# MINI-STM32.net
KiCad netlist of a schematic drawn in Altium Designer
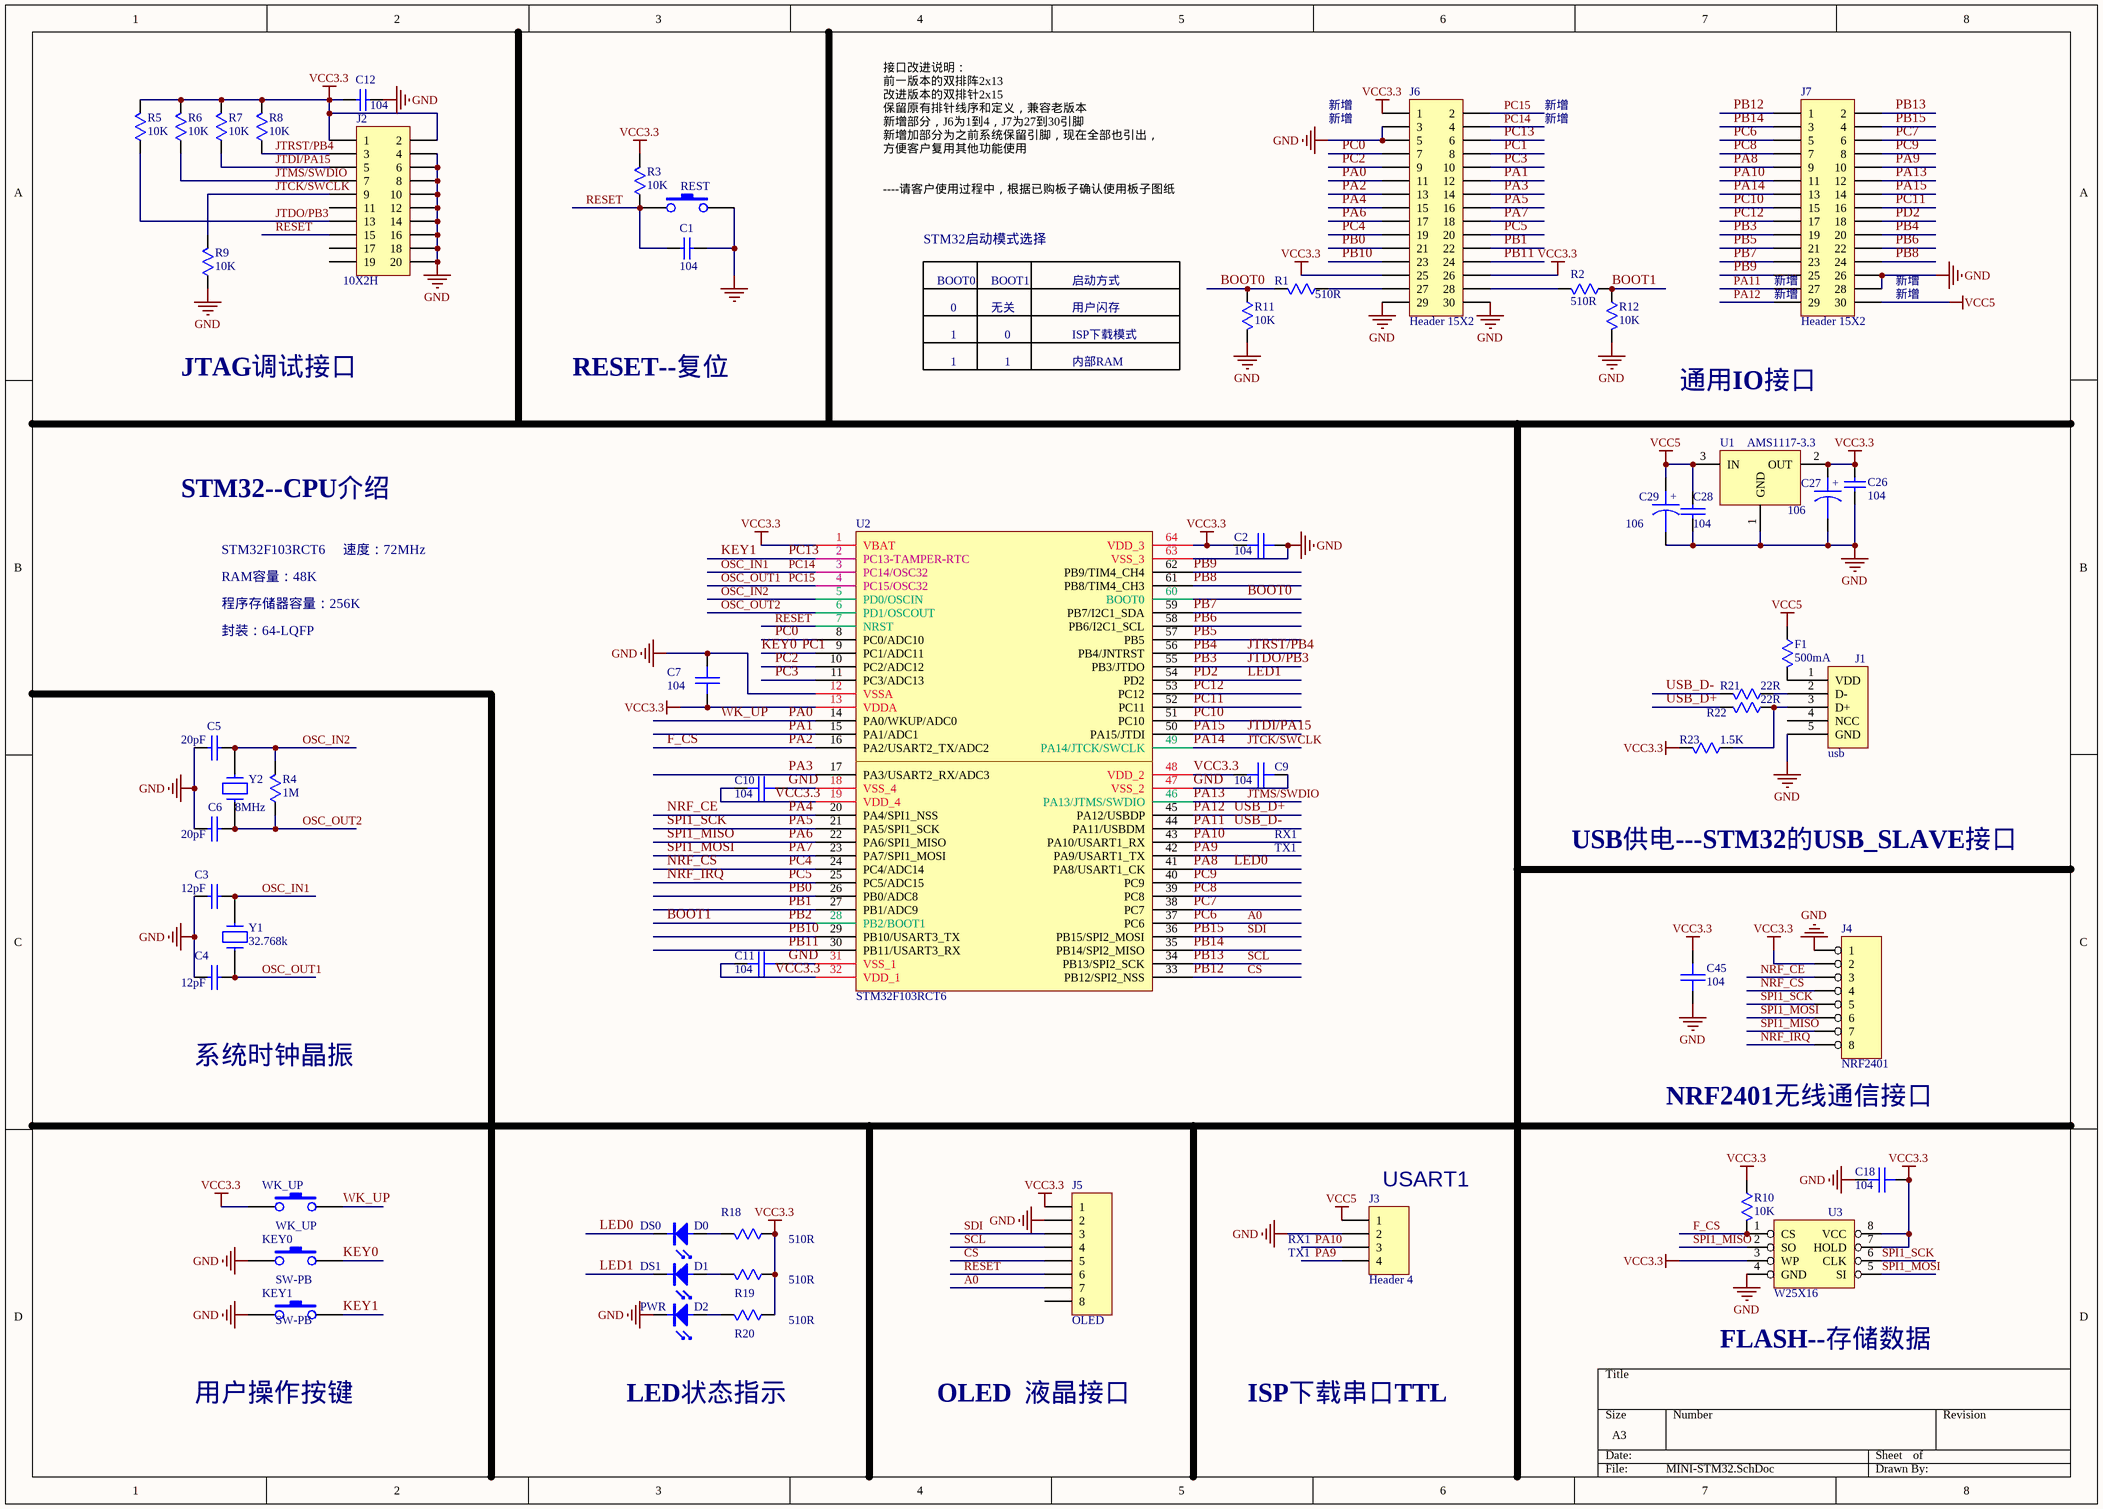
[diagram p0: MINI-STM32.SchDoc]

(export (version "E")
  (design (tool "Eeschema 10.0.6"))
  (components
    (comp (ref "C1")
      (value "104")
      (footprint "0603C")
      (description "GRM39 X7R102K50PT")
      (fields (field (name "PUBLISHER") "Altium Limited"))
      (libsource (lib "Miscellaneous Devices") (part "CAP"))
    )
    (comp (ref "C2") (value "104") (footprint "0603J") (libsource (lib "YT1_SCH_99SE") (part "CAP")))
    (comp (ref "C3")
      (value "12pF")
      (footprint "0603J")
      (description "CAP CHIP 20P 50V(+-5% C0G 0603)")
      (libsource (lib "") (part "CAP_1"))
    )
    (comp (ref "C4")
      (value "12pF")
      (footprint "0603J")
      (description "CAP CHIP 20P 50V(+-5% C0G 0603)")
      (libsource (lib "") (part "CAP_1"))
    )
    (comp (ref "C5")
      (value "20pF")
      (footprint "0603J")
      (description "CAP CHIP 20P 50V(+-5% C0G 0603)")
      (libsource (lib "") (part "CAP_1"))
    )
    (comp (ref "C6")
      (value "20pF")
      (footprint "0603J")
      (description "CAP CHIP 20P 50V(+-5% C0G 0603)")
      (libsource (lib "") (part "CAP_1"))
    )
    (comp (ref "C7") (value "104") (footprint "0603J") (libsource (lib "YT1_SCH_99SE") (part "CAP")))
    (comp (ref "C9") (value "104") (footprint "0603J") (libsource (lib "YT1_SCH_99SE") (part "CAP")))
    (comp (ref "C10") (value "104") (footprint "0603J") (libsource (lib "YT1_SCH_99SE") (part "CAP")))
    (comp (ref "C11") (value "104") (footprint "0603J") (libsource (lib "YT1_SCH_99SE") (part "CAP")))
    (comp (ref "C12")
      (value "104")
      (footprint "0603C")
      (description "GRM39 X7R102K50PT")
      (fields (field (name "PUBLISHER") "Altium Limited"))
      (libsource (lib "Miscellaneous Devices") (part "CAP"))
    )
    (comp (ref "C18") (value "104") (footprint "0603J") (libsource (lib "YT1_SCH_99SE") (part "CAP")))
    (comp (ref "C26")
      (value "104")
      (footprint "0603J")
      (description "Capacitor")
      (fields (field (name "PUBLISHER") "Altium Limited"))
      (libsource (lib "*") (part "Cap"))
    )
    (comp (ref "C27")
      (value "106")
      (footprint "RC0805")
      (description "Capacitor")
      (libsource (lib "*") (part "CAPACITOR POL"))
    )
    (comp (ref "C28")
      (value "104")
      (footprint "0603J")
      (description "Capacitor")
      (libsource (lib "*") (part "CAP"))
    )
    (comp (ref "C29")
      (value "106")
      (footprint "RC0805")
      (description "Capacitor")
      (libsource (lib "*") (part "CAPACITOR POL"))
    )
    (comp (ref "C45") (value "104") (footprint "0603J") (libsource (lib "YT1_SCH_99SE") (part "CAP")))
    (comp (ref "D0") (value "DS0") (footprint "LED0805") (libsource (lib "YT1_SCH_99SE") (part "LED")))
    (comp (ref "D1") (value "DS1") (footprint "LED0805") (libsource (lib "YT1_SCH_99SE") (part "LED")))
    (comp (ref "D2") (value "PWR") (footprint "LED0805") (libsource (lib "YT1_SCH_99SE") (part "LED")))
    (comp (ref "F1") (value "500mA") (footprint "RC0805") (libsource (lib "YT1_SCH_99SE") (part "RES")))
    (comp (ref "J1") (value "usb") (footprint "mini_USB") (libsource (lib "YT1_SCH_99SE") (part "usb")))
    (comp (ref "J2")
      (value "10X2H")
      (footprint "IDC20")
      (description "Header, 10-Pin, Dual row, Right Angle")
      (fields (field (name "PUBLISHER") "Altium Limited"))
      (libsource (lib "Miscellaneous Connectors") (part "Header 10X2H"))
    )
    (comp (ref "J3")
      (value "Header 4")
      (footprint "HDR1X4")
      (description "Header, 4-Pin")
      (fields (field (name "PUBLISHER") "Altium Limited"))
      (libsource (lib "Miscellaneous Connectors") (part "Header 4"))
    )
    (comp (ref "J4")
      (value "NRF2401")
      (footprint "HDR2X4")
      (description "8 Pin Header")
      (libsource (lib "YT1_SCH_99SE") (part "HEADER 8"))
    )
    (comp (ref "J5")
      (value "OLED")
      (footprint "HDR1X8")
      (description "Header, 8-Pin")
      (libsource (lib "Miscellaneous Connectors") (part "Header 8"))
    )
    (comp (ref "J6")
      (value "Header 15X2")
      (footprint "IDE15X2_2.54")
      (description "Header, 15-Pin, Dual row")
      (fields (field (name "PUBLISHER") "Altium Limited"))
      (libsource (lib "Miscellaneous Connectors") (part "Header 15X2"))
    )
    (comp (ref "J7")
      (value "Header 15X2")
      (footprint "IDE15X2_2.54")
      (description "Header, 15-Pin, Dual row")
      (fields (field (name "PUBLISHER") "Altium Limited"))
      (libsource (lib "Miscellaneous Connectors") (part "Header 15X2"))
    )
    (comp (ref "KEY0") (value "SW-PB") (footprint "SW-SPST") (libsource (lib "*") (part "SW-PB")))
    (comp (ref "KEY1") (value "SW-PB") (footprint "SW-SPST") (libsource (lib "*") (part "SW-PB")))
    (comp (ref "R1") (value "510R") (footprint "0603J") (libsource (lib "YT1_SCH_99SE") (part "RES")))
    (comp (ref "R2") (value "510R") (footprint "0603J") (libsource (lib "YT1_SCH_99SE") (part "RES")))
    (comp (ref "R3") (value "10K") (footprint "0603J") (libsource (lib "YT1_SCH_99SE") (part "RES")))
    (comp (ref "R4") (value "1M") (footprint "0603J") (libsource (lib "YT1_SCH_99SE") (part "RES")))
    (comp (ref "R5") (value "10K") (footprint "0603J") (libsource (lib "YT1_SCH_99SE") (part "RES")))
    (comp (ref "R6") (value "10K") (footprint "0603J") (libsource (lib "YT1_SCH_99SE") (part "RES")))
    (comp (ref "R7") (value "10K") (footprint "0603J") (libsource (lib "YT1_SCH_99SE") (part "RES")))
    (comp (ref "R8") (value "10K") (footprint "0603J") (libsource (lib "YT1_SCH_99SE") (part "RES")))
    (comp (ref "R9") (value "10K") (footprint "0603J") (libsource (lib "YT1_SCH_99SE") (part "RES")))
    (comp (ref "R10") (value "10K") (footprint "0603J") (libsource (lib "YT1_SCH_99SE") (part "RES")))
    (comp (ref "R11") (value "10K") (footprint "0603J") (libsource (lib "YT1_SCH_99SE") (part "RES")))
    (comp (ref "R12") (value "10K") (footprint "0603J") (libsource (lib "YT1_SCH_99SE") (part "RES")))
    (comp (ref "R18") (value "510R") (footprint "0603J") (libsource (lib "YT1_SCH_99SE") (part "RES")))
    (comp (ref "R19") (value "510R") (footprint "0603J") (libsource (lib "YT1_SCH_99SE") (part "RES")))
    (comp (ref "R20") (value "510R") (footprint "0603J") (libsource (lib "YT1_SCH_99SE") (part "RES")))
    (comp (ref "R21") (value "22R") (footprint "0603J") (libsource (lib "YT1_SCH_99SE") (part "RES")))
    (comp (ref "R22") (value "22R") (footprint "0603J") (libsource (lib "YT1_SCH_99SE") (part "RES")))
    (comp (ref "R23") (value "1.5K") (footprint "0603J") (libsource (lib "YT1_SCH_99SE") (part "RES")))
    (comp (ref "REST") (value "~") (footprint "SW-SPST") (libsource (lib "*") (part "SW-PB")))
    (comp (ref "U1")
      (value "AMS1117-3.3")
      (footprint "SOT223")
      (libsource (lib "Newcapec9263_Board_NEW") (part "LT1085CM-3.3"))
    )
    (comp (ref "U2")
      (value "STM32F103RCT6")
      (footprint "LQFP64")
      (libsource (lib "YT1_SCH_99SE") (part "STM32F103RBT6"))
    )
    (comp (ref "U3") (value "W25X16") (footprint "SOIC8P") (libsource (lib "YT1_SCH_99SE") (part "W25X16")))
    (comp (ref "WK_UP") (value "WK_UP") (footprint "SW-SPST") (libsource (lib "*") (part "SW-PB")))
    (comp (ref "Y1")
      (value "32.768k")
      (footprint "32.768k")
      (description "Crystal 8MHz PLUG")
      (libsource (lib "*") (part "CRYSTAL"))
    )
    (comp (ref "Y2")
      (value "8MHz")
      (footprint "smt-xtal")
      (description "Crystal 8MHz PLUG")
      (libsource (lib "*") (part "CRYSTAL"))
    )
  )
  (nets
    (net (code "1") (name "/A0") (class "Default")
      (node (ref "J5") (pin "7") (pinfunction "7_7") (pintype "passive"))
      (node (ref "J7") (pin "5") (pinfunction "5_5") (pintype "passive"))
      (node (ref "U2") (pin "37") (pinfunction "PC6_37") (pintype "passive"))
    )
    (net (code "2") (name "/BOOT0") (class "Default")
      (node (ref "R1") (pin "2") (pinfunction "2_2") (pintype "passive"))
      (node (ref "R11") (pin "1") (pinfunction "1_1") (pintype "passive"))
      (node (ref "U2") (pin "60") (pinfunction "BOOT0_60") (pintype "passive"))
    )
    (net (code "3") (name "/BOOT1") (class "Default")
      (node (ref "R12") (pin "1") (pinfunction "1_1") (pintype "passive"))
      (node (ref "R2") (pin "1") (pinfunction "1_1") (pintype "passive"))
      (node (ref "U2") (pin "28") (pinfunction "PB2/BOOT1_28") (pintype "passive"))
    )
    (net (code "4") (name "/CS") (class "Default")
      (node (ref "J5") (pin "5") (pinfunction "5_5") (pintype "passive"))
      (node (ref "J7") (pin "1") (pinfunction "1_1") (pintype "passive"))
      (node (ref "U2") (pin "33") (pinfunction "PB12/SPI2_NSS_33") (pintype "passive"))
    )
    (net (code "5") (name "/F_CS") (class "Default")
      (node (ref "J6") (pin "13") (pinfunction "13_13") (pintype "passive"))
      (node (ref "R10") (pin "2") (pinfunction "2_2") (pintype "passive"))
      (node (ref "U2") (pin "16") (pinfunction "PA2/USART2_TX/ADC2_16") (pintype "passive"))
      (node (ref "U3") (pin "1") (pinfunction "CS_1") (pintype "passive"))
    )
    (net (code "6") (name "/JTCK{slash}SWCLK") (class "Default")
      (node (ref "J2") (pin "9") (pinfunction "9_9") (pintype "passive"))
      (node (ref "J7") (pin "13") (pinfunction "13_13") (pintype "passive"))
      (node (ref "R9") (pin "2") (pinfunction "2_2") (pintype "passive"))
      (node (ref "U2") (pin "49") (pinfunction "PA14/JTCK/SWCLK_49") (pintype "passive"))
    )
    (net (code "7") (name "/JTDI{slash}PA15") (class "Default")
      (node (ref "J2") (pin "5") (pinfunction "5_5") (pintype "passive"))
      (node (ref "J7") (pin "14") (pinfunction "14_14") (pintype "passive"))
      (node (ref "R7") (pin "1") (pinfunction "1_1") (pintype "passive"))
      (node (ref "U2") (pin "50") (pinfunction "PA15/JTDI_50") (pintype "passive"))
    )
    (net (code "8") (name "/JTDO{slash}PB3") (class "Default")
      (node (ref "J2") (pin "13") (pinfunction "13_13") (pintype "passive"))
      (node (ref "J7") (pin "19") (pinfunction "19_19") (pintype "passive"))
      (node (ref "R5") (pin "1") (pinfunction "1_1") (pintype "passive"))
      (node (ref "U2") (pin "55") (pinfunction "PB3/JTDO_55") (pintype "passive"))
    )
    (net (code "9") (name "/JTMS{slash}SWDIO") (class "Default")
      (node (ref "J2") (pin "7") (pinfunction "7_7") (pintype "passive"))
      (node (ref "J7") (pin "12") (pinfunction "12_12") (pintype "passive"))
      (node (ref "R6") (pin "1") (pinfunction "1_1") (pintype "passive"))
      (node (ref "U2") (pin "46") (pinfunction "PA13/JTMS/SWDIO_46") (pintype "passive"))
    )
    (net (code "10") (name "/JTRST{slash}PB4") (class "Default")
      (node (ref "J2") (pin "3") (pinfunction "3_3") (pintype "passive"))
      (node (ref "J7") (pin "20") (pinfunction "20_20") (pintype "passive"))
      (node (ref "R8") (pin "1") (pinfunction "1_1") (pintype "passive"))
      (node (ref "U2") (pin "56") (pinfunction "PB4/JNTRST_56") (pintype "passive"))
    )
    (net (code "11") (name "/KEY0") (class "Default")
      (node (ref "J6") (pin "8") (pinfunction "8_8") (pintype "passive"))
      (node (ref "KEY0") (pin "2") (pinfunction "2_2") (pintype "passive"))
      (node (ref "U2") (pin "9") (pinfunction "PC1/ADC11_9") (pintype "passive"))
    )
    (net (code "12") (name "/KEY1") (class "Default")
      (node (ref "J6") (pin "6") (pinfunction "6_6") (pintype "passive"))
      (node (ref "KEY1") (pin "2") (pinfunction "2_2") (pintype "passive"))
      (node (ref "U2") (pin "2") (pinfunction "PC13-TAMPER-RTC_2") (pintype "passive"))
    )
    (net (code "13") (name "/LED0") (class "Default")
      (node (ref "D0") (pin "2") (pinfunction "2_2") (pintype "passive"))
      (node (ref "J7") (pin "9") (pinfunction "9_9") (pintype "passive"))
      (node (ref "U2") (pin "41") (pinfunction "PA8/USART1_CK_41") (pintype "passive"))
    )
    (net (code "14") (name "/LED1") (class "Default")
      (node (ref "D1") (pin "2") (pinfunction "2_2") (pintype "passive"))
      (node (ref "J7") (pin "18") (pinfunction "18_18") (pintype "passive"))
      (node (ref "U2") (pin "54") (pinfunction "PD2_54") (pintype "passive"))
    )
    (net (code "15") (name "/NRF_CE") (class "Default")
      (node (ref "J4") (pin "3") (pinfunction "3_3") (pintype "passive"))
      (node (ref "J6") (pin "15") (pinfunction "15_15") (pintype "passive"))
      (node (ref "U2") (pin "20") (pinfunction "PA4/SPI1_NSS_20") (pintype "passive"))
    )
    (net (code "16") (name "/NRF_CS") (class "Default")
      (node (ref "J4") (pin "4") (pinfunction "4_4") (pintype "passive"))
      (node (ref "J6") (pin "19") (pinfunction "19_19") (pintype "passive"))
      (node (ref "U2") (pin "24") (pinfunction "PC4/ADC14_24") (pintype "passive"))
    )
    (net (code "17") (name "/NRF_IRQ") (class "Default")
      (node (ref "J4") (pin "8") (pinfunction "8_8") (pintype "passive"))
      (node (ref "J6") (pin "20") (pinfunction "20_20") (pintype "passive"))
      (node (ref "U2") (pin "25") (pinfunction "PC5/ADC15_25") (pintype "passive"))
    )
    (net (code "18") (name "/OSC_IN1") (class "Default")
      (node (ref "C3") (pin "2") (pinfunction "2_2") (pintype "passive"))
      (node (ref "J6") (pin "4") (pinfunction "4_4") (pintype "passive"))
      (node (ref "U2") (pin "3") (pinfunction "PC14/OSC32_3") (pintype "passive"))
      (node (ref "Y1") (pin "2") (pinfunction "2_2") (pintype "passive"))
    )
    (net (code "19") (name "/OSC_IN2") (class "Default")
      (node (ref "C5") (pin "2") (pinfunction "2_2") (pintype "passive"))
      (node (ref "R4") (pin "2") (pinfunction "2_2") (pintype "passive"))
      (node (ref "U2") (pin "5") (pinfunction "PD0/OSCIN_5") (pintype "passive"))
      (node (ref "Y2") (pin "1") (pinfunction "1_1") (pintype "passive"))
    )
    (net (code "20") (name "/OSC_OUT1") (class "Default")
      (node (ref "C4") (pin "2") (pinfunction "2_2") (pintype "passive"))
      (node (ref "J6") (pin "2") (pinfunction "2_2") (pintype "passive"))
      (node (ref "U2") (pin "4") (pinfunction "PC15/OSC32_4") (pintype "passive"))
      (node (ref "Y1") (pin "1") (pinfunction "1_1") (pintype "passive"))
    )
    (net (code "21") (name "/OSC_OUT2") (class "Default")
      (node (ref "C6") (pin "2") (pinfunction "2_2") (pintype "passive"))
      (node (ref "R4") (pin "1") (pinfunction "1_1") (pintype "passive"))
      (node (ref "U2") (pin "6") (pinfunction "PD1/OSCOUT_6") (pintype "passive"))
      (node (ref "Y2") (pin "2") (pinfunction "2_2") (pintype "passive"))
    )
    (net (code "22") (name "/PA0") (class "Default")
      (node (ref "J6") (pin "11") (pinfunction "11_11") (pintype "passive"))
      (node (ref "U2") (pin "14") (pinfunction "PA0/WKUP/ADC0_14") (pintype "passive"))
      (node (ref "WK_UP") (pin "2") (pinfunction "2_2") (pintype "passive"))
    )
    (net (code "23") (name "/PA1") (class "Default")
      (node (ref "J6") (pin "12") (pinfunction "12_12") (pintype "passive"))
      (node (ref "U2") (pin "15") (pinfunction "PA1/ADC1_15") (pintype "passive"))
    )
    (net (code "24") (name "/PA3") (class "Default")
      (node (ref "J6") (pin "14") (pinfunction "14_14") (pintype "passive"))
      (node (ref "U2") (pin "17") (pinfunction "PA3/USART2_RX/ADC3_17") (pintype "passive"))
    )
    (net (code "25") (name "/PA5") (class "Default")
      (node (ref "J4") (pin "5") (pinfunction "5_5") (pintype "passive"))
      (node (ref "J6") (pin "16") (pinfunction "16_16") (pintype "passive"))
      (node (ref "U2") (pin "21") (pinfunction "PA5/SPI1_SCK_21") (pintype "passive"))
      (node (ref "U3") (pin "6") (pinfunction "CLK_6") (pintype "passive"))
    )
    (net (code "26") (name "/PA6") (class "Default")
      (node (ref "J4") (pin "7") (pinfunction "7_7") (pintype "passive"))
      (node (ref "J6") (pin "17") (pinfunction "17_17") (pintype "passive"))
      (node (ref "U2") (pin "22") (pinfunction "PA6/SPI1_MISO_22") (pintype "passive"))
      (node (ref "U3") (pin "2") (pinfunction "SO_2") (pintype "passive"))
    )
    (net (code "27") (name "/PA7") (class "Default")
      (node (ref "J4") (pin "6") (pinfunction "6_6") (pintype "passive"))
      (node (ref "J6") (pin "18") (pinfunction "18_18") (pintype "passive"))
      (node (ref "U2") (pin "23") (pinfunction "PA7/SPI1_MOSI_23") (pintype "passive"))
      (node (ref "U3") (pin "5") (pinfunction "SI_5") (pintype "passive"))
    )
    (net (code "28") (name "/PA9") (class "Default")
      (node (ref "J3") (pin "4") (pinfunction "4_4") (pintype "passive"))
      (node (ref "J7") (pin "10") (pinfunction "10_10") (pintype "passive"))
      (node (ref "U2") (pin "42") (pinfunction "PA9/USART1_TX_42") (pintype "passive"))
    )
    (net (code "29") (name "/PA10") (class "Default")
      (node (ref "J3") (pin "3") (pinfunction "3_3") (pintype "passive"))
      (node (ref "J7") (pin "11") (pinfunction "11_11") (pintype "passive"))
      (node (ref "U2") (pin "43") (pinfunction "PA10/USART1_RX_43") (pintype "passive"))
    )
    (net (code "30") (name "/PA11") (class "Default")
      (node (ref "J7") (pin "27") (pinfunction "27_27") (pintype "passive"))
      (node (ref "R21") (pin "2") (pinfunction "2_2") (pintype "passive"))
      (node (ref "U2") (pin "44") (pinfunction "PA11/USBDM_44") (pintype "passive"))
    )
    (net (code "31") (name "/PA12") (class "Default")
      (node (ref "J7") (pin "29") (pinfunction "29_29") (pintype "passive"))
      (node (ref "R22") (pin "2") (pinfunction "2_2") (pintype "passive"))
      (node (ref "U2") (pin "45") (pinfunction "PA12/USBDP_45") (pintype "passive"))
    )
    (net (code "32") (name "/PB0") (class "Default")
      (node (ref "J6") (pin "21") (pinfunction "21_21") (pintype "passive"))
      (node (ref "U2") (pin "26") (pinfunction "PB0/ADC8_26") (pintype "passive"))
    )
    (net (code "33") (name "/PB1") (class "Default")
      (node (ref "J6") (pin "22") (pinfunction "22_22") (pintype "passive"))
      (node (ref "U2") (pin "27") (pinfunction "PB1/ADC9_27") (pintype "passive"))
    )
    (net (code "34") (name "/PB5") (class "Default")
      (node (ref "J7") (pin "21") (pinfunction "21_21") (pintype "passive"))
      (node (ref "U2") (pin "57") (pinfunction "PB5_57") (pintype "passive"))
    )
    (net (code "35") (name "/PB6") (class "Default")
      (node (ref "J7") (pin "22") (pinfunction "22_22") (pintype "passive"))
      (node (ref "U2") (pin "58") (pinfunction "PB6/I2C1_SCL_58") (pintype "passive"))
    )
    (net (code "36") (name "/PB7") (class "Default")
      (node (ref "J7") (pin "23") (pinfunction "23_23") (pintype "passive"))
      (node (ref "U2") (pin "59") (pinfunction "PB7/I2C1_SDA_59") (pintype "passive"))
    )
    (net (code "37") (name "/PB8") (class "Default")
      (node (ref "J7") (pin "24") (pinfunction "24_24") (pintype "passive"))
      (node (ref "U2") (pin "61") (pinfunction "PB8/TIM4_CH3_61") (pintype "passive"))
    )
    (net (code "38") (name "/PB9") (class "Default")
      (node (ref "J7") (pin "25") (pinfunction "25_25") (pintype "passive"))
      (node (ref "U2") (pin "62") (pinfunction "PB9/TIM4_CH4_62") (pintype "passive"))
    )
    (net (code "39") (name "/PB10") (class "Default")
      (node (ref "J6") (pin "23") (pinfunction "23_23") (pintype "passive"))
      (node (ref "U2") (pin "29") (pinfunction "PB10/USART3_TX_29") (pintype "passive"))
    )
    (net (code "40") (name "/PB11") (class "Default")
      (node (ref "J6") (pin "24") (pinfunction "24_24") (pintype "passive"))
      (node (ref "U2") (pin "30") (pinfunction "PB11/USART3_RX_30") (pintype "passive"))
    )
    (net (code "41") (name "/PB13") (class "Default")
      (node (ref "J5") (pin "4") (pinfunction "4_4") (pintype "passive"))
      (node (ref "J7") (pin "2") (pinfunction "2_2") (pintype "passive"))
      (node (ref "U2") (pin "34") (pinfunction "PB13/SPI2_SCK_34") (pintype "passive"))
    )
    (net (code "42") (name "/PB14") (class "Default")
      (node (ref "J7") (pin "3") (pinfunction "3_3") (pintype "passive"))
      (node (ref "U2") (pin "35") (pinfunction "PB14/SPI2_MISO_35") (pintype "passive"))
    )
    (net (code "43") (name "/PB15") (class "Default")
      (node (ref "J5") (pin "3") (pinfunction "3_3") (pintype "passive"))
      (node (ref "J7") (pin "4") (pinfunction "4_4") (pintype "passive"))
      (node (ref "U2") (pin "36") (pinfunction "PB15/SPI2_MOSI_36") (pintype "passive"))
    )
    (net (code "44") (name "/PC0") (class "Default")
      (node (ref "J6") (pin "7") (pinfunction "7_7") (pintype "passive"))
      (node (ref "U2") (pin "8") (pinfunction "PC0/ADC10_8") (pintype "passive"))
    )
    (net (code "45") (name "/PC2") (class "Default")
      (node (ref "J6") (pin "9") (pinfunction "9_9") (pintype "passive"))
      (node (ref "U2") (pin "10") (pinfunction "PC2/ADC12_10") (pintype "passive"))
    )
    (net (code "46") (name "/PC3") (class "Default")
      (node (ref "J6") (pin "10") (pinfunction "10_10") (pintype "passive"))
      (node (ref "U2") (pin "11") (pinfunction "PC3/ADC13_11") (pintype "passive"))
    )
    (net (code "47") (name "/PC7") (class "Default")
      (node (ref "J7") (pin "6") (pinfunction "6_6") (pintype "passive"))
      (node (ref "U2") (pin "38") (pinfunction "PC7_38") (pintype "passive"))
    )
    (net (code "48") (name "/PC8") (class "Default")
      (node (ref "J7") (pin "7") (pinfunction "7_7") (pintype "passive"))
      (node (ref "U2") (pin "39") (pinfunction "PC8_39") (pintype "passive"))
    )
    (net (code "49") (name "/PC9") (class "Default")
      (node (ref "J7") (pin "8") (pinfunction "8_8") (pintype "passive"))
      (node (ref "U2") (pin "40") (pinfunction "PC9_40") (pintype "passive"))
    )
    (net (code "50") (name "/PC10") (class "Default")
      (node (ref "J7") (pin "15") (pinfunction "15_15") (pintype "passive"))
      (node (ref "U2") (pin "51") (pinfunction "PC10_51") (pintype "passive"))
    )
    (net (code "51") (name "/PC11") (class "Default")
      (node (ref "J7") (pin "16") (pinfunction "16_16") (pintype "passive"))
      (node (ref "U2") (pin "52") (pinfunction "PC11_52") (pintype "passive"))
    )
    (net (code "52") (name "/PC12") (class "Default")
      (node (ref "J7") (pin "17") (pinfunction "17_17") (pintype "passive"))
      (node (ref "U2") (pin "53") (pinfunction "PC12_53") (pintype "passive"))
    )
    (net (code "53") (name "/RESET") (class "Default")
      (node (ref "C1") (pin "2") (pinfunction "2_2") (pintype "passive"))
      (node (ref "J2") (pin "15") (pinfunction "15_15") (pintype "passive"))
      (node (ref "J5") (pin "6") (pinfunction "6_6") (pintype "passive"))
      (node (ref "R3") (pin "1") (pinfunction "1_1") (pintype "passive"))
      (node (ref "REST") (pin "1") (pinfunction "1_1") (pintype "passive"))
      (node (ref "U2") (pin "7") (pinfunction "NRST_7") (pintype "passive"))
    )
    (net (code "54") (name "GND") (class "Default")
      (node (ref "C1") (pin "1") (pinfunction "1_1") (pintype "passive"))
      (node (ref "C10") (pin "2") (pinfunction "2_2") (pintype "passive"))
      (node (ref "C11") (pin "2") (pinfunction "2_2") (pintype "passive"))
      (node (ref "C12") (pin "2") (pinfunction "2_2") (pintype "passive"))
      (node (ref "C18") (pin "1") (pinfunction "1_1") (pintype "passive"))
      (node (ref "C2") (pin "2") (pinfunction "2_2") (pintype "passive"))
      (node (ref "C26") (pin "2") (pinfunction "2_2") (pintype "passive"))
      (node (ref "C27") (pin "2") (pinfunction "2_2") (pintype "passive"))
      (node (ref "C28") (pin "2") (pinfunction "2_2") (pintype "passive"))
      (node (ref "C29") (pin "2") (pinfunction "2_2") (pintype "passive"))
      (node (ref "C3") (pin "1") (pinfunction "1_1") (pintype "passive"))
      (node (ref "C4") (pin "1") (pinfunction "1_1") (pintype "passive"))
      (node (ref "C45") (pin "2") (pinfunction "2_2") (pintype "passive"))
      (node (ref "C5") (pin "1") (pinfunction "1_1") (pintype "passive"))
      (node (ref "C6") (pin "1") (pinfunction "1_1") (pintype "passive"))
      (node (ref "C7") (pin "1") (pinfunction "1_1") (pintype "passive"))
      (node (ref "C9") (pin "2") (pinfunction "2_2") (pintype "passive"))
      (node (ref "D2") (pin "2") (pinfunction "2_2") (pintype "passive"))
      (node (ref "J1") (pin "5") (pinfunction "GND_5") (pintype "passive"))
      (node (ref "J2") (pin "10") (pinfunction "10_10") (pintype "passive"))
      (node (ref "J2") (pin "12") (pinfunction "12_12") (pintype "passive"))
      (node (ref "J2") (pin "14") (pinfunction "14_14") (pintype "passive"))
      (node (ref "J2") (pin "16") (pinfunction "16_16") (pintype "passive"))
      (node (ref "J2") (pin "18") (pinfunction "18_18") (pintype "passive"))
      (node (ref "J2") (pin "20") (pinfunction "20_20") (pintype "passive"))
      (node (ref "J2") (pin "4") (pinfunction "4_4") (pintype "passive"))
      (node (ref "J2") (pin "6") (pinfunction "6_6") (pintype "passive"))
      (node (ref "J2") (pin "8") (pinfunction "8_8") (pintype "passive"))
      (node (ref "J3") (pin "2") (pinfunction "2_2") (pintype "passive"))
      (node (ref "J4") (pin "1") (pinfunction "1_1") (pintype "passive"))
      (node (ref "J5") (pin "2") (pinfunction "2_2") (pintype "passive"))
      (node (ref "J6") (pin "29") (pinfunction "29_29") (pintype "passive"))
      (node (ref "J6") (pin "3") (pinfunction "3_3") (pintype "passive"))
      (node (ref "J6") (pin "30") (pinfunction "30_30") (pintype "passive"))
      (node (ref "J6") (pin "5") (pinfunction "5_5") (pintype "passive"))
      (node (ref "J7") (pin "26") (pinfunction "26_26") (pintype "passive"))
      (node (ref "J7") (pin "28") (pinfunction "28_28") (pintype "passive"))
      (node (ref "KEY0") (pin "1") (pinfunction "1_1") (pintype "passive"))
      (node (ref "KEY1") (pin "1") (pinfunction "1_1") (pintype "passive"))
      (node (ref "R11") (pin "2") (pinfunction "2_2") (pintype "passive"))
      (node (ref "R12") (pin "2") (pinfunction "2_2") (pintype "passive"))
      (node (ref "R9") (pin "1") (pinfunction "1_1") (pintype "passive"))
      (node (ref "REST") (pin "2") (pinfunction "2_2") (pintype "passive"))
      (node (ref "U1") (pin "1") (pinfunction "GND_1") (pintype "passive"))
      (node (ref "U2") (pin "12") (pinfunction "VSSA_12") (pintype "passive"))
      (node (ref "U2") (pin "18") (pinfunction "VSS_4_18") (pintype "passive"))
      (node (ref "U2") (pin "31") (pinfunction "VSS_1_31") (pintype "passive"))
      (node (ref "U2") (pin "47") (pinfunction "VSS_2_47") (pintype "passive"))
      (node (ref "U2") (pin "63") (pinfunction "VSS_3_63") (pintype "passive"))
      (node (ref "U3") (pin "4") (pinfunction "GND_4") (pintype "passive"))
    )
    (net (code "55") (name "Net-(D0-Pad1)") (class "Default")
      (node (ref "D0") (pin "1") (pinfunction "1_1") (pintype "passive"))
      (node (ref "R18") (pin "2") (pinfunction "2_2") (pintype "passive"))
    )
    (net (code "56") (name "Net-(D1-Pad1)") (class "Default")
      (node (ref "D1") (pin "1") (pinfunction "1_1") (pintype "passive"))
      (node (ref "R19") (pin "2") (pinfunction "2_2") (pintype "passive"))
    )
    (net (code "57") (name "Net-(D2-Pad1)") (class "Default")
      (node (ref "D2") (pin "1") (pinfunction "1_1") (pintype "passive"))
      (node (ref "R20") (pin "2") (pinfunction "2_2") (pintype "passive"))
    )
    (net (code "58") (name "Net-(J1-D+)") (class "Default")
      (node (ref "J1") (pin "3") (pinfunction "D+_3") (pintype "passive"))
      (node (ref "R22") (pin "1") (pinfunction "1_1") (pintype "passive"))
      (node (ref "R23") (pin "1") (pinfunction "1_1") (pintype "passive"))
    )
    (net (code "59") (name "Net-(J1-D-)") (class "Default")
      (node (ref "J1") (pin "2") (pinfunction "D-_2") (pintype "passive"))
      (node (ref "R21") (pin "1") (pinfunction "1_1") (pintype "passive"))
    )
    (net (code "60") (name "Net-(J1-VDD)") (class "Default")
      (node (ref "F1") (pin "2") (pinfunction "2_2") (pintype "passive"))
      (node (ref "J1") (pin "1") (pinfunction "VDD_1") (pintype "passive"))
    )
    (net (code "61") (name "Net-(J6-Pad27)") (class "Default")
      (node (ref "J6") (pin "27") (pinfunction "27_27") (pintype "passive"))
      (node (ref "R1") (pin "1") (pinfunction "1_1") (pintype "passive"))
    )
    (net (code "62") (name "Net-(J6-Pad28)") (class "Default")
      (node (ref "J6") (pin "28") (pinfunction "28_28") (pintype "passive"))
      (node (ref "R2") (pin "2") (pinfunction "2_2") (pintype "passive"))
    )
    (net (code "63") (name "VCC3.3") (class "Default")
      (node (ref "C10") (pin "1") (pinfunction "1_1") (pintype "passive"))
      (node (ref "C11") (pin "1") (pinfunction "1_1") (pintype "passive"))
      (node (ref "C12") (pin "1") (pinfunction "1_1") (pintype "passive"))
      (node (ref "C18") (pin "2") (pinfunction "2_2") (pintype "passive"))
      (node (ref "C2") (pin "1") (pinfunction "1_1") (pintype "passive"))
      (node (ref "C26") (pin "1") (pinfunction "1_1") (pintype "passive"))
      (node (ref "C27") (pin "1") (pinfunction "1_1") (pintype "passive"))
      (node (ref "C45") (pin "1") (pinfunction "1_1") (pintype "passive"))
      (node (ref "C7") (pin "2") (pinfunction "2_2") (pintype "passive"))
      (node (ref "C9") (pin "1") (pinfunction "1_1") (pintype "passive"))
      (node (ref "J2") (pin "1") (pinfunction "1_1") (pintype "passive"))
      (node (ref "J2") (pin "2") (pinfunction "2_2") (pintype "passive"))
      (node (ref "J4") (pin "2") (pinfunction "2_2") (pintype "passive"))
      (node (ref "J5") (pin "1") (pinfunction "1_1") (pintype "passive"))
      (node (ref "J6") (pin "1") (pinfunction "1_1") (pintype "passive"))
      (node (ref "J6") (pin "25") (pinfunction "25_25") (pintype "passive"))
      (node (ref "J6") (pin "26") (pinfunction "26_26") (pintype "passive"))
      (node (ref "R10") (pin "1") (pinfunction "1_1") (pintype "passive"))
      (node (ref "R18") (pin "1") (pinfunction "1_1") (pintype "passive"))
      (node (ref "R19") (pin "1") (pinfunction "1_1") (pintype "passive"))
      (node (ref "R20") (pin "1") (pinfunction "1_1") (pintype "passive"))
      (node (ref "R23") (pin "2") (pinfunction "2_2") (pintype "passive"))
      (node (ref "R3") (pin "2") (pinfunction "2_2") (pintype "passive"))
      (node (ref "R5") (pin "2") (pinfunction "2_2") (pintype "passive"))
      (node (ref "R6") (pin "2") (pinfunction "2_2") (pintype "passive"))
      (node (ref "R7") (pin "2") (pinfunction "2_2") (pintype "passive"))
      (node (ref "R8") (pin "2") (pinfunction "2_2") (pintype "passive"))
      (node (ref "U1") (pin "2") (pinfunction "OUT_2") (pintype "passive"))
      (node (ref "U2") (pin "1") (pinfunction "VBAT_1") (pintype "passive"))
      (node (ref "U2") (pin "13") (pinfunction "VDDA_13") (pintype "passive"))
      (node (ref "U2") (pin "19") (pinfunction "VDD_4_19") (pintype "passive"))
      (node (ref "U2") (pin "32") (pinfunction "VDD_1_32") (pintype "passive"))
      (node (ref "U2") (pin "48") (pinfunction "VDD_2_48") (pintype "passive"))
      (node (ref "U2") (pin "64") (pinfunction "VDD_3_64") (pintype "passive"))
      (node (ref "U3") (pin "3") (pinfunction "WP_3") (pintype "passive"))
      (node (ref "U3") (pin "7") (pinfunction "HOLD_7") (pintype "passive"))
      (node (ref "U3") (pin "8") (pinfunction "VCC_8") (pintype "passive"))
      (node (ref "WK_UP") (pin "1") (pinfunction "1_1") (pintype "passive"))
    )
    (net (code "64") (name "VCC5") (class "Default")
      (node (ref "C28") (pin "1") (pinfunction "1_1") (pintype "passive"))
      (node (ref "C29") (pin "1") (pinfunction "1_1") (pintype "passive"))
      (node (ref "F1") (pin "1") (pinfunction "1_1") (pintype "passive"))
      (node (ref "J3") (pin "1") (pinfunction "1_1") (pintype "passive"))
      (node (ref "J7") (pin "30") (pinfunction "30_30") (pintype "passive"))
      (node (ref "U1") (pin "3") (pinfunction "IN_3") (pintype "passive"))
    )
    (net (code "65") (name "unconnected-(J1-NCC-Pad4)") (class "Default")
      (node (ref "J1") (pin "4") (pinfunction "NCC_4") (pintype "passive"))
    )
    (net (code "66") (name "unconnected-(J2-Pad11)") (class "Default")
      (node (ref "J2") (pin "11") (pinfunction "11_11") (pintype "passive"))
    )
    (net (code "67") (name "unconnected-(J2-Pad17)") (class "Default")
      (node (ref "J2") (pin "17") (pinfunction "17_17") (pintype "passive"))
    )
    (net (code "68") (name "unconnected-(J2-Pad19)") (class "Default")
      (node (ref "J2") (pin "19") (pinfunction "19_19") (pintype "passive"))
    )
    (net (code "69") (name "unconnected-(J5-Pad8)") (class "Default")
      (node (ref "J5") (pin "8") (pinfunction "8_8") (pintype "passive"))
    )
  )
)
